# TIDA-01560_BlankSheet.net
KiCad netlist of a schematic drawn in Altium Designer
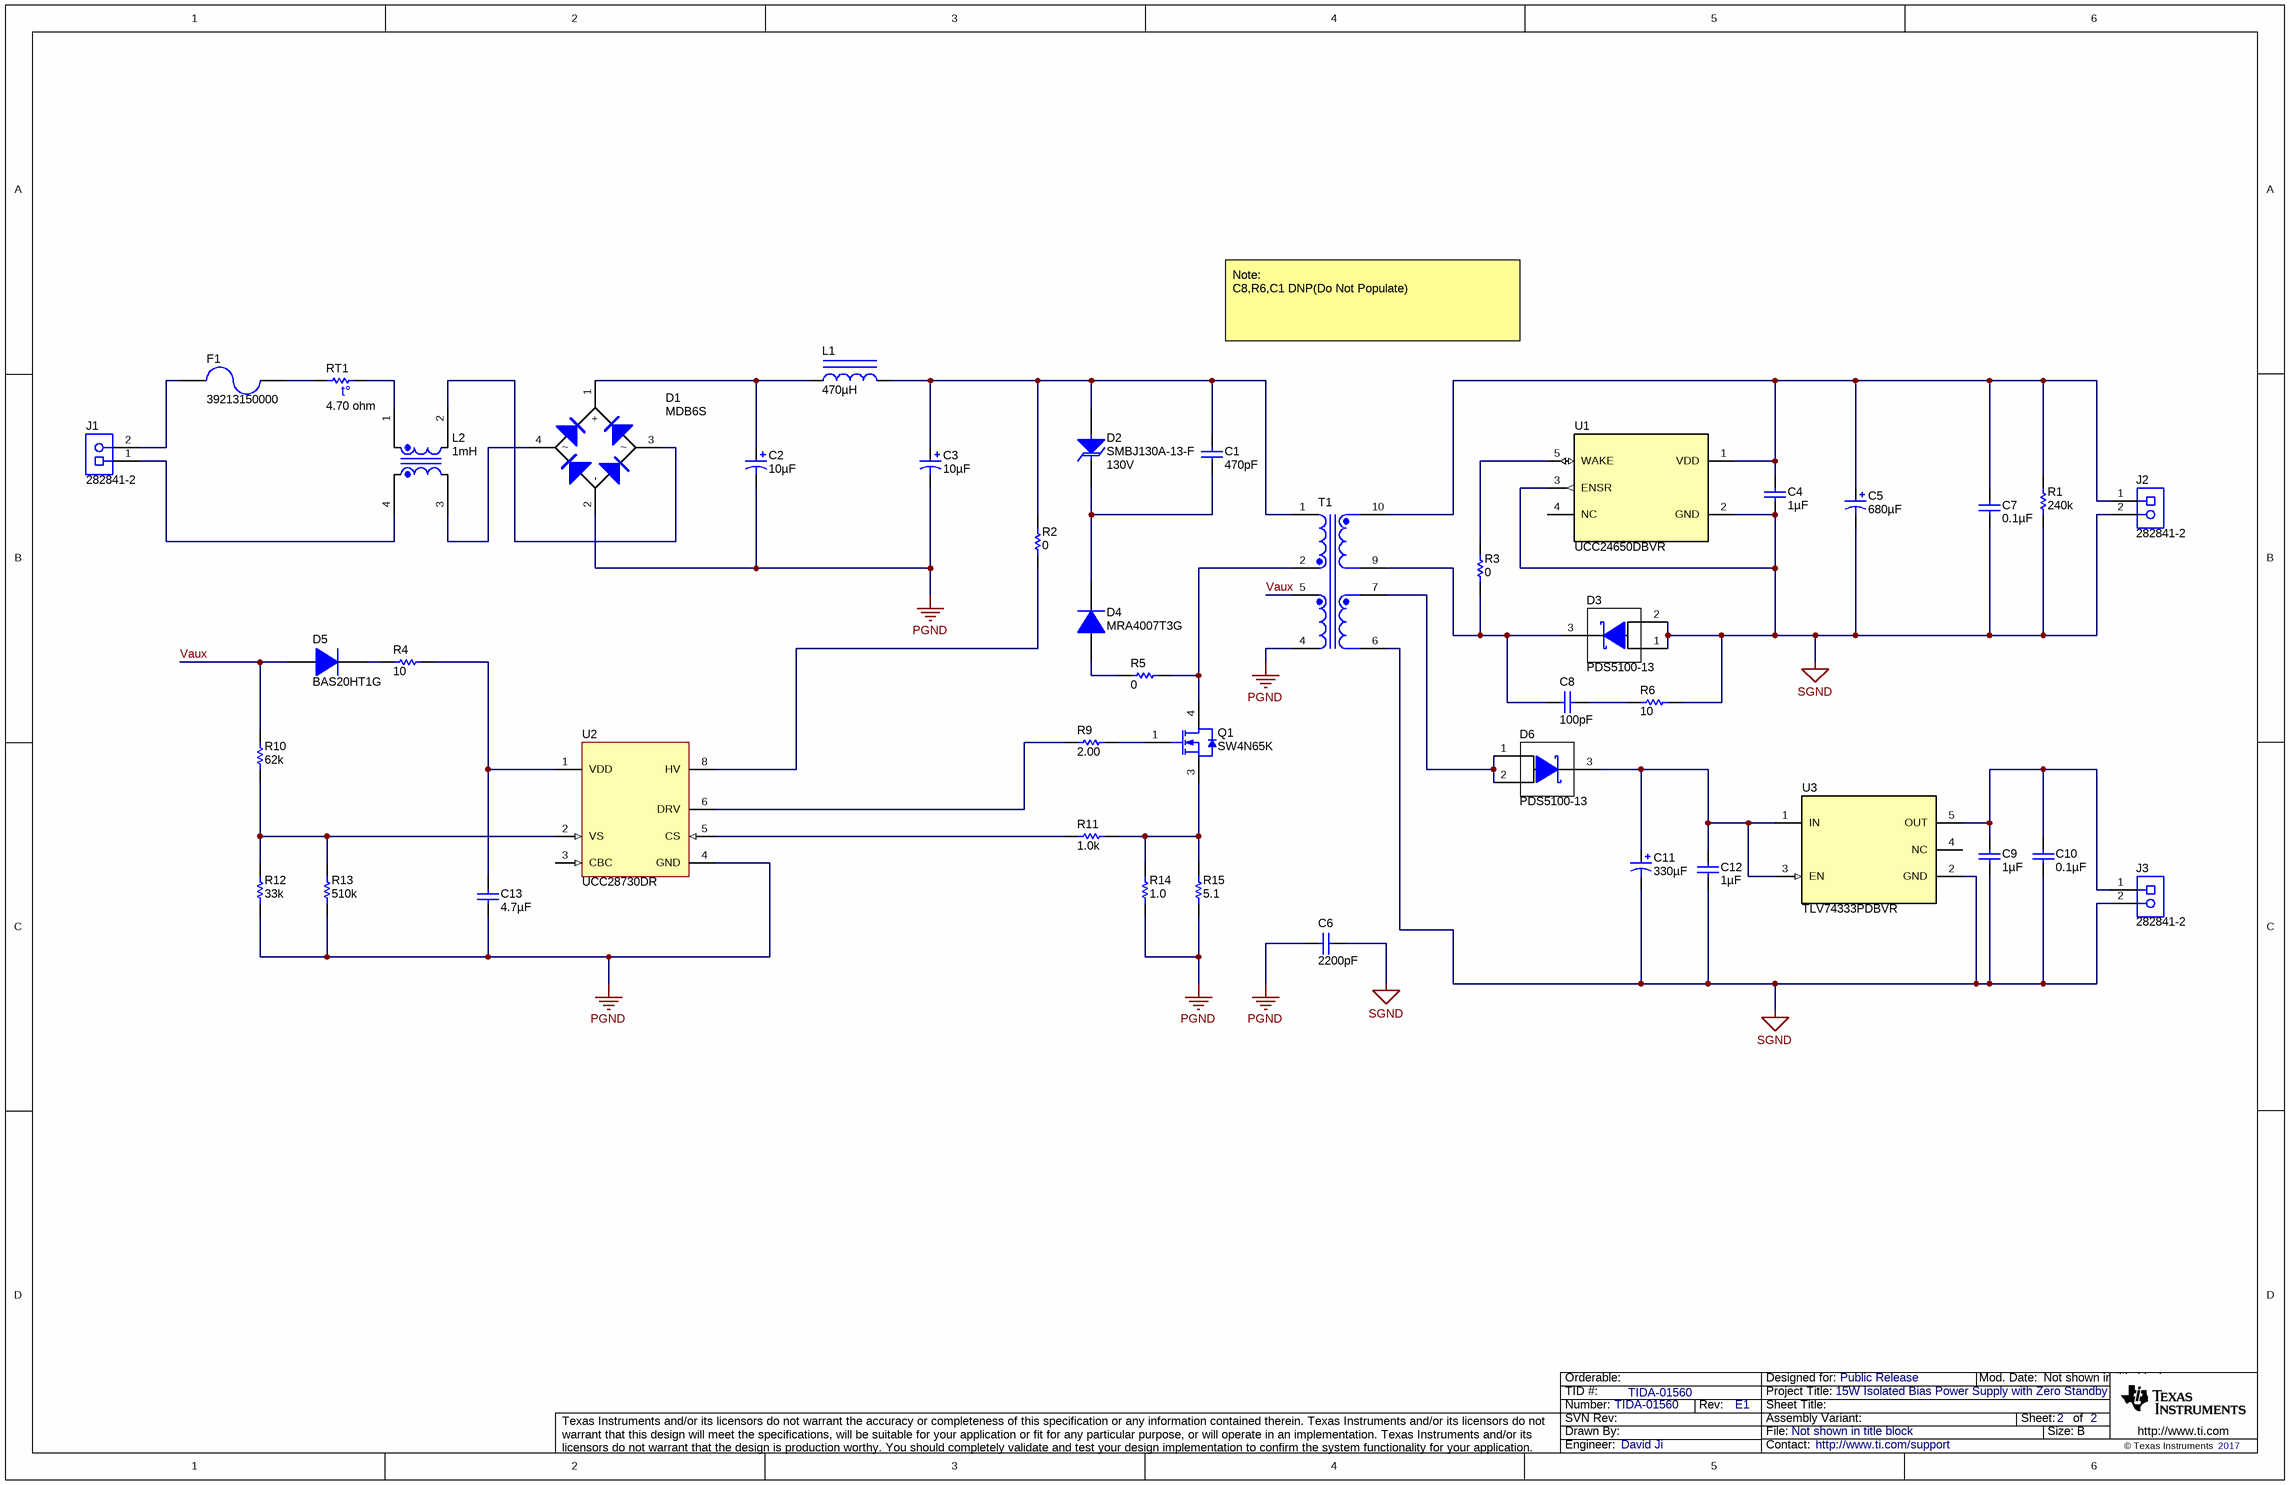
[diagram p0: TIDA-01560_BlankSheet.SchDoc]

(export (version "E")
  (design (tool "Eeschema 10.0.6"))
  (components
    (comp (ref "C1")
      (value "GRM31A7U2J471JW31D")
      (footprint "1206")
      (description "CAP, CERM, 470 pF, 630 V, +/- 5%, U2J, 1206")
      (fields
        (field (name "VALUEDISPLAYED") "470pF")
        (field (name "MANUFACTURER") "MuRata")
        (field (name "PUBLISHER") "Texas Instruments")
      )
      (libsource (lib "Capacitor_Ceramic") (part "GRM31A7U2J471JW31D"))
    )
    (comp (ref "C2")
      (value "UCY2G100MPD1TD")
      (footprint "CY_1000x1600")
      (description "CAP, AL, 10 µF, 400 V, +/- 20%, TH")
      (fields
        (field (name "VALUEDISPLAYED") "10µF")
        (field (name "MANUFACTURER") "Nichicon")
        (field (name "PUBLISHER") "Texas Instruments")
      )
      (libsource (lib "Capacitor_Aluminum") (part "UCY2G100MPD1TD"))
    )
    (comp (ref "C3")
      (value "UCY2G100MPD1TD")
      (footprint "CY_1000x1600")
      (description "CAP, AL, 10 µF, 400 V, +/- 20%, TH")
      (fields
        (field (name "VALUEDISPLAYED") "10µF")
        (field (name "MANUFACTURER") "Nichicon")
        (field (name "PUBLISHER") "Texas Instruments")
      )
      (libsource (lib "Capacitor_Aluminum") (part "UCY2G100MPD1TD"))
    )
    (comp (ref "C4")
      (value "06033C105KAT2A")
      (footprint "0603")
      (description "CAP, CERM, 1 µF, 25 V,+/- 10%, X7R, 0603")
      (fields
        (field (name "VALUEDISPLAYED") "1µF")
        (field (name "MANUFACTURER") "AVX")
        (field (name "PUBLISHER") "Texas Instruments")
      )
      (libsource (lib "Capacitor_Ceramic") (part "06033C105KAT2A"))
    )
    (comp (ref "C5")
      (value "APSG200ELL681MJB5S")
      (footprint "R7_1000x1250")
      (description "CAP, AL, 680 µF, 20 V, +/- 20%, 0.012 ohm, TH")
      (fields
        (field (name "VALUEDISPLAYED") "680µF")
        (field (name "MANUFACTURER") "Chemi-Con")
        (field (name "PUBLISHER") "Texas Instruments")
      )
      (libsource (lib "Capacitor_Aluminum") (part "RR71C331MDN1"))
    )
    (comp (ref "C6")
      (value "DE1E3KX222MN5AA01")
      (footprint "KX_1000x800x1400")
      (description "CAP, CERM, 2200 pF, X1 250 VAC/Y1 300 VAC, +/- 20%, E, 10.0x8.0x14.0mm")
      (fields
        (field (name "VALUEDISPLAYED") "2200pF")
        (field (name "MANUFACTURER") "MuRata")
        (field (name "PUBLISHER") "Texas Instruments")
      )
      (libsource (lib "Capacitor_Ceramic") (part "DE1E3KX222MN5AA01"))
    )
    (comp (ref "C7")
      (value "C0603C104K3RACTU")
      (footprint "0603")
      (description "CAP, CERM, 0.1 µF, 25 V,+/- 10%, X7R, 0603")
      (fields
        (field (name "VALUEDISPLAYED") "0.1µF")
        (field (name "MANUFACTURER") "Kemet")
        (field (name "PUBLISHER") "Texas Instruments")
      )
      (libsource (lib "Capacitor_Ceramic") (part "C0603C104K3RACTU"))
    )
    (comp (ref "C8")
      (value "GCM2165C2A101JA16D")
      (footprint "0805_HV")
      (description "CAP, CERM, 100 pF, 100 V,+/- 5%, C0G/NP0, AEC-Q200 Grade 1, 0805")
      (fields
        (field (name "VALUEDISPLAYED") "100pF")
        (field (name "MANUFACTURER") "MuRata")
        (field (name "PUBLISHER") "Texas Instruments")
      )
      (libsource (lib "Capacitor_Ceramic") (part "GCM2165C2A101JA16D"))
    )
    (comp (ref "C9")
      (value "C1608X7R1E105K080AB")
      (footprint "0603")
      (description "CAP, CERM, 1 µF, 25 V,+/- 10%, X7R, 0603")
      (fields
        (field (name "VALUEDISPLAYED") "1µF")
        (field (name "MANUFACTURER") "TDK")
        (field (name "PUBLISHER") "Texas Instruments")
      )
      (libsource (lib "Capacitor_Ceramic") (part "C1608X7R1E105K080AB"))
    )
    (comp (ref "C10")
      (value "C0603C104K3RACTU")
      (footprint "0603")
      (description "CAP, CERM, 0.1 µF, 25 V,+/- 10%, X7R, 0603")
      (fields
        (field (name "VALUEDISPLAYED") "0.1µF")
        (field (name "MANUFACTURER") "Kemet")
        (field (name "PUBLISHER") "Texas Instruments")
      )
      (libsource (lib "Capacitor_Ceramic") (part "C0603C104K3RACTU"))
    )
    (comp (ref "C11")
      (value "875105144010")
      (footprint "SM_RADIAL_6.3AMM")
      (description "CAP, AL, 330 µF, 6.3 V, +/- 20%, 0.020 ohm, SMD")
      (fields
        (field (name "VALUEDISPLAYED") "330µF")
        (field (name "MANUFACTURER") "Wurth Elektronik")
        (field (name "PUBLISHER") "Texas Instruments")
      )
      (libsource (lib "Capacitor_Aluminum") (part "UUD0J221MCL1GS"))
    )
    (comp (ref "C12")
      (value "C1608X7R1E105K080AB")
      (footprint "0603")
      (description "CAP, CERM, 1 µF, 25 V,+/- 10%, X7R, 0603")
      (fields
        (field (name "VALUEDISPLAYED") "1µF")
        (field (name "MANUFACTURER") "TDK")
        (field (name "PUBLISHER") "Texas Instruments")
      )
      (libsource (lib "Capacitor_Ceramic") (part "C1608X7R1E105K080AB"))
    )
    (comp (ref "C13")
      (value "C3216X7R1H475K160AC")
      (footprint "1206_180")
      (description "CAP, CERM, 4.7 µF, 50 V,+/- 10%, X7R, 1206")
      (fields
        (field (name "VALUEDISPLAYED") "4.7µF")
        (field (name "MANUFACTURER") "TDK")
        (field (name "PUBLISHER") "Texas Instruments")
      )
      (libsource (lib "Capacitor_Ceramic") (part "C3216X7R1H475K160AC"))
    )
    (comp (ref "D1")
      (value "MDB6S")
      (footprint "MICRODIP_4")
      (description "Diode, Switching-Bridge, 600 V, 1 A, MICRODIP_4")
      (fields
        (field (name "MANUFACTURER") "Fairchild Semiconductor")
        (field (name "PUBLISHER") "Texas Instruments")
      )
      (libsource (lib "Diode") (part "MDB6S"))
    )
    (comp (ref "D2")
      (value "SMBJ130A-13-F")
      (footprint "SMB")
      (description "Diode, TVS, Uni, 130 V, 209 Vc, SMB")
      (fields
        (field (name "ALTIUM_VALUE") "130V")
        (field (name "MANUFACTURER") "Diodes Inc.")
        (field (name "PUBLISHER") "Texas Instruments")
      )
      (libsource (lib "ZenerDiodes") (part "SMBJ130A-13-F"))
    )
    (comp (ref "D3")
      (value "PDS5100-13")
      (footprint "PowerDI5")
      (description "Diode, Schottky, 100 V, 5 A, PowerDI5")
      (fields (field (name "MANUFACTURER") "Diodes Inc.") (field (name "PUBLISHER") "Texas Instruments"))
      (libsource (lib "") (part "PDS5100-13_1"))
    )
    (comp (ref "D4")
      (value "MRA4007T3G")
      (footprint "SMA")
      (description "Diode, Standard Recovery Rectifier, 1000 V, 1 A, AEC-Q101, SMA")
      (fields (field (name "MANUFACTURER") "ON Semiconductor") (field (name "PUBLISHER") "Texas Instruments"))
      (libsource (lib "Diode") (part "MRA4007T3G"))
    )
    (comp (ref "D5")
      (value "BAS20HT1G")
      (footprint "sod-323")
      (description "Diode, Switching, 200 V, 0.2 A, AEC-Q101, SOD-323")
      (fields (field (name "MANUFACTURER") "ON Semiconductor") (field (name "PUBLISHER") "Texas Instruments"))
      (libsource (lib "Diode") (part "BAS20HT1G"))
    )
    (comp (ref "D6")
      (value "PDS5100-13")
      (footprint "PowerDI5")
      (description "Diode, Schottky, 100 V, 5 A, PowerDI5")
      (fields (field (name "MANUFACTURER") "Diodes Inc.") (field (name "PUBLISHER") "Texas Instruments"))
      (libsource (lib "Diode") (part "PDS5100-13"))
    )
    (comp (ref "F1")
      (value "39213150000")
      (footprint "FUSE_392")
      (description "Fuse, 3.15 A, 250VAC/VDC, TH")
      (fields (field (name "MANUFACTURER") "Littelfuse") (field (name "PUBLISHER") "Texas Instruments"))
      (libsource (lib "Fuse") (part "39213150000"))
    )
    (comp (ref "J1")
      (value "282841-2")
      (footprint "TEC_282841-2")
      (description "Terminal Block, 2x1, 5.08mm, TH")
      (fields
        (field (name "MANUFACTURER") "TE Connectivity")
        (field (name "SYMBOLCREATOR") "a0412235")
        (field (name "PUBLISHER") "Texas Instruments")
      )
      (libsource (lib "") (part "282841-2_1"))
    )
    (comp (ref "J2")
      (value "282841-2")
      (footprint "TEC_282841-2")
      (description "Terminal Block, 2x1, 5.08mm, TH")
      (fields
        (field (name "MANUFACTURER") "TE Connectivity")
        (field (name "SYMBOLCREATOR") "a0412235")
        (field (name "PUBLISHER") "Texas Instruments")
      )
      (libsource (lib "Connectors_TE_Connectivity") (part "282841-2"))
    )
    (comp (ref "J3")
      (value "282841-2")
      (footprint "TEC_282841-2")
      (description "Terminal Block, 2x1, 5.08mm, TH")
      (fields
        (field (name "MANUFACTURER") "TE Connectivity")
        (field (name "SYMBOLCREATOR") "a0412235")
        (field (name "PUBLISHER") "Texas Instruments")
      )
      (libsource (lib "Connectors_TE_Connectivity") (part "282841-2"))
    )
    (comp (ref "L1")
      (value "7447462471")
      (footprint "WE-TI_5075")
      (description "Inductor, Unshielded Drum Core, Ferrite, 470 µH, 0.35 A, 1.58 ohm, TH")
      (fields
        (field (name "VALUEDISPLAYED") "470µH")
        (field (name "MANUFACTURER") "Wurth Elektronik")
        (field (name "PUBLISHER") "Texas Instruments")
      )
      (libsource (lib "Inductor_Wurth") (part "7447462471"))
    )
    (comp (ref "L2")
      (value "744821201")
      (footprint "WE-CMB_XS")
      (description "Coupled inductor, 1 mH, 2 A, 0.045 ohm, TH")
      (fields
        (field (name "VALUEDISPLAYED") "1mH")
        (field (name "MANUFACTURER") "Wurth Elektronik")
        (field (name "SYMBOLCREATOR") "a0412235")
        (field (name "PUBLISHER") "Texas Instruments")
      )
      (libsource (lib "Coupled_Inductors") (part "744821201"))
    )
    (comp (ref "Q1")
      (value "SW4N65K")
      (footprint "TO-252")
      (description "MOSFET, N-CH, 650 V, 4 A, TO-252")
      (fields (field (name "MANUFACTURER") "IXYS") (field (name "PUBLISHER") "Texas Instruments"))
      (libsource (lib "FETs") (part "IXTY02N120P"))
    )
    (comp (ref "R1")
      (value "CRCW0805240KJNEA")
      (footprint "0805_HV")
      (description "RES, 240 k, 5%, 0.125 W, 0805")
      (fields
        (field (name "VALUEDISPLAYED") "240k")
        (field (name "MANUFACTURER") "Vishay-Dale")
        (field (name "PUBLISHER") "Texas Instruments")
      )
      (libsource (lib "Resistor_0805") (part "CRCW0805240KJNEA"))
    )
    (comp (ref "R2")
      (value "CRCW12060000Z0EA")
      (footprint "1206")
      (description "RES, 0, 5%, 0.25 W, 1206")
      (fields
        (field (name "VALUEDISPLAYED") "0")
        (field (name "MANUFACTURER") "Vishay-Dale")
        (field (name "PUBLISHER") "Texas Instruments")
      )
      (libsource (lib "Resistor_1206") (part "CRCW12060000Z0EA"))
    )
    (comp (ref "R3")
      (value "CRCW08050000Z0EA")
      (footprint "0805_HV")
      (description "RES, 0, 5%, 0.125 W, 0805")
      (fields
        (field (name "VALUEDISPLAYED") "0")
        (field (name "MANUFACTURER") "Vishay-Dale")
        (field (name "PUBLISHER") "Texas Instruments")
      )
      (libsource (lib "Resistor_0805") (part "CRCW08050000Z0EA"))
    )
    (comp (ref "R4")
      (value "CRCW080510R0JNEA")
      (footprint "0805_HV")
      (description "RES, 10, 5%, 0.125 W, 0805")
      (fields
        (field (name "VALUEDISPLAYED") "10")
        (field (name "MANUFACTURER") "Vishay-Dale")
        (field (name "PUBLISHER") "Texas Instruments")
      )
      (libsource (lib "Resistor_0805") (part "CRCW080510R0JNEA"))
    )
    (comp (ref "R5")
      (value "CRCW12060000Z0EA")
      (footprint "1206")
      (description "RES, 0, 5%, 0.25 W, 1206")
      (fields
        (field (name "VALUEDISPLAYED") "0")
        (field (name "MANUFACTURER") "Vishay-Dale")
        (field (name "PUBLISHER") "Texas Instruments")
      )
      (libsource (lib "Resistor_1206") (part "CRCW12060000Z0EA"))
    )
    (comp (ref "R6")
      (value "CRCW120610R0JNEA")
      (footprint "1206")
      (description "RES, 10, 5%, 0.25 W, 1206")
      (fields
        (field (name "VALUEDISPLAYED") "10")
        (field (name "MANUFACTURER") "Vishay-Dale")
        (field (name "PUBLISHER") "Texas Instruments")
      )
      (libsource (lib "Resistor_1206") (part "CRCW120610R0JNEA"))
    )
    (comp (ref "R9")
      (value "CRCW06032R00FKEA")
      (footprint "0603")
      (description "RES, 2.00, 1%, 0.1 W, 0603")
      (fields
        (field (name "VALUEDISPLAYED") "2.00")
        (field (name "MANUFACTURER") "Vishay-Dale")
        (field (name "PUBLISHER") "Texas Instruments")
      )
      (libsource (lib "Resistor_0603") (part "CRCW06032R00FKEA"))
    )
    (comp (ref "R10")
      (value "CRCW080562K0JNEA")
      (footprint "0805_HV")
      (description "RES, 62 k, 5%, 0.125 W, 0805")
      (fields
        (field (name "VALUEDISPLAYED") "62k")
        (field (name "MANUFACTURER") "Vishay-Dale")
        (field (name "PUBLISHER") "Texas Instruments")
      )
      (libsource (lib "Resistor_0805") (part "CRCW080562K0JNEA"))
    )
    (comp (ref "R11")
      (value "CRCW06031K00JNEA")
      (footprint "0603")
      (description "RES, 1.0 k, 5%, 0.1 W, 0603")
      (fields
        (field (name "VALUEDISPLAYED") "1.0k")
        (field (name "MANUFACTURER") "Vishay-Dale")
        (field (name "PUBLISHER") "Texas Instruments")
      )
      (libsource (lib "Resistor_0603") (part "CRCW06031K00JNEA"))
    )
    (comp (ref "R12")
      (value "CRCW060333K0JNEA")
      (footprint "0603")
      (description "RES, 33 k, 5%, 0.1 W, 0603")
      (fields
        (field (name "VALUEDISPLAYED") "33k")
        (field (name "MANUFACTURER") "Vishay-Dale")
        (field (name "PUBLISHER") "Texas Instruments")
      )
      (libsource (lib "Resistor_0603") (part "CRCW060333K0JNEA"))
    )
    (comp (ref "R13")
      (value "CRCW0603510KJNEA")
      (footprint "0603")
      (description "RES, 510 k, 5%, 0.1 W, 0603")
      (fields
        (field (name "VALUEDISPLAYED") "510k")
        (field (name "MANUFACTURER") "Vishay-Dale")
        (field (name "PUBLISHER") "Texas Instruments")
      )
      (libsource (lib "Resistor_0603") (part "CRCW0603510KJNEA"))
    )
    (comp (ref "R14")
      (value "CRCW08051R00JNEA")
      (footprint "0805_HV")
      (description "RES, 1.0, 5%, 0.125 W, 0805")
      (fields
        (field (name "VALUEDISPLAYED") "1.0")
        (field (name "MANUFACTURER") "Vishay-Dale")
        (field (name "PUBLISHER") "Texas Instruments")
      )
      (libsource (lib "Resistor_0805") (part "CRCW08051R00JNEA"))
    )
    (comp (ref "R15")
      (value "CRCW08055R10JNEA")
      (footprint "0805_HV")
      (description "RES, 5.1, 5%, 0.125 W, 0805")
      (fields
        (field (name "VALUEDISPLAYED") "5.1")
        (field (name "MANUFACTURER") "Vishay-Dale")
        (field (name "PUBLISHER") "Texas Instruments")
      )
      (libsource (lib "Resistor_0805") (part "CRCW08055R10JNEA"))
    )
    (comp (ref "RT1")
      (value "4.70 ohm")
      (footprint "S153")
      (description "Thermistor NTC, 4.70 ohm, 20%, 8.5mm Disc")
      (fields
        (field (name "PARTNUMBER") "B57153S0479M051")
        (field (name "MANUFACTURER") "TDK")
        (field (name "PUBLISHER") "Texas Instruments")
      )
      (libsource (lib "ThermistorNTC") (part "B57153S0479M051"))
    )
    (comp (ref "T1")
      (value "750343769,Rev02")
      (footprint "EFD20 Transformer:PCBComponent_1")
      (description "Transformer, 620uH, TH")
      (fields (field (name "MANUFACTURER") "Wurth Elektronik") (field (name "SYMBOLCREATOR") "Use a-id"))
      (libsource (lib "EFD20 Transformer") (part "Component_1"))
    )
    (comp (ref "U1")
      (value "UCC24650DBVR")
      (footprint "DBV0005A_N")
      (description "200-V Wake-Up Monitor for Fast Transient PSR, DBV0005A")
      (fields
        (field (name "ALTERNATE PARTNUMBER") "UCC24650DBVT")
        (field (name "MANUFACTURER") "Texas Instruments")
        (field (name "SYMBOLCREATOR") "x0208326")
        (field (name "PUBLISHER") "Texas Instruments")
      )
      (libsource (lib "TI_Pre_Release") (part "UCC24650DBVR"))
    )
    (comp (ref "U2")
      (value "UCC28730DR")
      (footprint "D0007A_N")
      (description "Constant-Voltage Constant-Current Flyback Controller With PSR and Wake-Up Monitoring, D0007A")
      (fields
        (field (name "ALTERNATE PARTNUMBER") "UCC28730D")
        (field (name "MANUFACTURER") "Texas Instruments")
        (field (name "SYMBOLCREATOR") "x0208325")
        (field (name "PUBLISHER") "Texas Instruments")
      )
      (libsource (lib "TI_Pre_Release1") (part "UCC28730DR"))
    )
    (comp (ref "U3")
      (value "TLV74333PDBVR")
      (footprint "DBV0005A_N")
      (description "Low-Dropout Regulator, DBV0005A (SOT-23-5)")
      (fields
        (field (name "MANUFACTURER") "Texas Instruments")
        (field (name "SYMBOLCREATOR") "Altium")
        (field (name "PUBLISHER") "Texas Instruments")
      )
      (libsource (lib "TI_Pre_RTM") (part "TLV74333PDBVR"))
    )
  )
  (nets
    (net (code "1") (name "/Vaux") (class "Default")
      (node (ref "D5") (pin "2") (pinfunction "A_2") (pintype "passive"))
      (node (ref "R10") (pin "1") (pinfunction "1_1") (pintype "passive"))
      (node (ref "T1") (pin "5") (pinfunction "5_5") (pintype "passive"))
    )
    (net (code "2") (name "Net-(C2-+)") (class "Default")
      (node (ref "C2") (pin "1") (pinfunction "+_1") (pintype "passive"))
      (node (ref "D1") (pin "1") (pinfunction "+_1") (pintype "passive"))
      (node (ref "L1") (pin "1") (pinfunction "1_1") (pintype "passive"))
    )
    (net (code "3") (name "Net-(C3-+)") (class "Default")
      (node (ref "C1") (pin "1") (pinfunction "1_1") (pintype "passive"))
      (node (ref "C3") (pin "1") (pinfunction "+_1") (pintype "passive"))
      (node (ref "D2") (pin "2") (pinfunction "A_2") (pintype "passive"))
      (node (ref "L1") (pin "2") (pinfunction "2_2") (pintype "passive"))
      (node (ref "R2") (pin "2") (pinfunction "2_2") (pintype "passive"))
      (node (ref "T1") (pin "1") (pinfunction "1_1") (pintype "passive"))
    )
    (net (code "4") (name "Net-(C5-+)") (class "Default")
      (node (ref "C4") (pin "1") (pinfunction "1_1") (pintype "passive"))
      (node (ref "C5") (pin "1") (pinfunction "+_1") (pintype "passive"))
      (node (ref "C7") (pin "1") (pinfunction "1_1") (pintype "passive"))
      (node (ref "J2") (pin "1") (pinfunction "1_1") (pintype "passive"))
      (node (ref "R1") (pin "2") (pinfunction "2_2") (pintype "passive"))
      (node (ref "T1") (pin "10") (pinfunction "10_10") (pintype "passive"))
      (node (ref "U1") (pin "1") (pinfunction "VDD_1") (pintype "power_in"))
    )
    (net (code "5") (name "Net-(C8-Pad1)") (class "Default")
      (node (ref "C8") (pin "1") (pinfunction "1_1") (pintype "passive"))
      (node (ref "R6") (pin "1") (pinfunction "1_1") (pintype "passive"))
    )
    (net (code "6") (name "Net-(C11-+)") (class "Default")
      (node (ref "C11") (pin "1") (pinfunction "+_1") (pintype "passive"))
      (node (ref "C12") (pin "1") (pinfunction "1_1") (pintype "passive"))
      (node (ref "D6") (pin "3") (pinfunction "K_3") (pintype "passive"))
      (node (ref "U3") (pin "1") (pinfunction "IN_1") (pintype "power_in"))
      (node (ref "U3") (pin "3") (pinfunction "EN_3") (pintype "input"))
    )
    (net (code "7") (name "Net-(D1-~-Pad3)") (class "Default")
      (node (ref "D1") (pin "3") (pinfunction "~_3") (pintype "passive"))
      (node (ref "L2") (pin "2") (pinfunction "2_2") (pintype "passive"))
    )
    (net (code "8") (name "Net-(D1-~-Pad4)") (class "Default")
      (node (ref "D1") (pin "4") (pinfunction "~_4") (pintype "passive"))
      (node (ref "L2") (pin "3") (pinfunction "3_3") (pintype "passive"))
    )
    (net (code "9") (name "Net-(D2-K)") (class "Default")
      (node (ref "C1") (pin "2") (pinfunction "2_2") (pintype "passive"))
      (node (ref "D2") (pin "1") (pinfunction "K_1") (pintype "passive"))
      (node (ref "D4") (pin "1") (pinfunction "K_1") (pintype "passive"))
    )
    (net (code "10") (name "Net-(D3-K)") (class "Default")
      (node (ref "C8") (pin "2") (pinfunction "2_2") (pintype "passive"))
      (node (ref "D3") (pin "3") (pinfunction "K_3") (pintype "passive"))
      (node (ref "R3") (pin "1") (pinfunction "1_1") (pintype "passive"))
      (node (ref "T1") (pin "9") (pinfunction "9_9") (pintype "passive"))
    )
    (net (code "11") (name "Net-(D4-A)") (class "Default")
      (node (ref "D4") (pin "2") (pinfunction "A_2") (pintype "passive"))
      (node (ref "R5") (pin "1") (pinfunction "1_1") (pintype "passive"))
    )
    (net (code "12") (name "Net-(D5-K)") (class "Default")
      (node (ref "D5") (pin "1") (pinfunction "K_1") (pintype "passive"))
      (node (ref "R4") (pin "1") (pinfunction "1_1") (pintype "passive"))
    )
    (net (code "13") (name "Net-(D6-A-Pad1)") (class "Default")
      (node (ref "D6") (pin "1") (pinfunction "A_1") (pintype "passive"))
      (node (ref "D6") (pin "2") (pinfunction "A_2") (pintype "passive"))
      (node (ref "T1") (pin "7") (pinfunction "7_7") (pintype "passive"))
    )
    (net (code "14") (name "Net-(F1-Pad1)") (class "Default")
      (node (ref "F1") (pin "1") (pinfunction "1_1") (pintype "passive"))
      (node (ref "RT1") (pin "1") (pinfunction "1_1") (pintype "passive"))
    )
    (net (code "15") (name "Net-(F1-Pad2)") (class "Default")
      (node (ref "F1") (pin "2") (pinfunction "2_2") (pintype "passive"))
      (node (ref "J1") (pin "2") (pinfunction "2_2") (pintype "passive"))
    )
    (net (code "16") (name "Net-(J1-Pad1)") (class "Default")
      (node (ref "J1") (pin "1") (pinfunction "1_1") (pintype "passive"))
      (node (ref "L2") (pin "4") (pinfunction "4_4") (pintype "passive"))
    )
    (net (code "17") (name "Net-(L2-Pad1)") (class "Default")
      (node (ref "L2") (pin "1") (pinfunction "1_1") (pintype "passive"))
      (node (ref "RT1") (pin "2") (pinfunction "2_2") (pintype "passive"))
    )
    (net (code "18") (name "Net-(Q1-D)") (class "Default")
      (node (ref "Q1") (pin "4") (pinfunction "D_4") (pintype "passive"))
      (node (ref "R5") (pin "2") (pinfunction "2_2") (pintype "passive"))
      (node (ref "T1") (pin "2") (pinfunction "2_2") (pintype "passive"))
    )
    (net (code "19") (name "Net-(Q1-G)") (class "Default")
      (node (ref "Q1") (pin "1") (pinfunction "G_1") (pintype "passive"))
      (node (ref "R9") (pin "2") (pinfunction "2_2") (pintype "passive"))
    )
    (net (code "20") (name "Net-(Q1-S)") (class "Default")
      (node (ref "Q1") (pin "3") (pinfunction "S_3") (pintype "passive"))
      (node (ref "R11") (pin "2") (pinfunction "2_2") (pintype "passive"))
      (node (ref "R14") (pin "2") (pinfunction "2_2") (pintype "passive"))
      (node (ref "R15") (pin "2") (pinfunction "2_2") (pintype "passive"))
    )
    (net (code "21") (name "Net-(U1-WAKE)") (class "Default")
      (node (ref "R3") (pin "2") (pinfunction "2_2") (pintype "passive"))
      (node (ref "U1") (pin "5") (pinfunction "WAKE_5") (pintype "bidirectional"))
    )
    (net (code "22") (name "Net-(U2-CS)") (class "Default")
      (node (ref "R11") (pin "1") (pinfunction "1_1") (pintype "passive"))
      (node (ref "U2") (pin "5") (pinfunction "CS_5") (pintype "input"))
    )
    (net (code "23") (name "Net-(U2-DRV)") (class "Default")
      (node (ref "R9") (pin "1") (pinfunction "1_1") (pintype "passive"))
      (node (ref "U2") (pin "6") (pinfunction "DRV_6") (pintype "power_in"))
    )
    (net (code "24") (name "Net-(U2-HV)") (class "Default")
      (node (ref "R2") (pin "1") (pinfunction "1_1") (pintype "passive"))
      (node (ref "U2") (pin "8") (pinfunction "HV_8") (pintype "power_in"))
    )
    (net (code "25") (name "Net-(U2-VDD)") (class "Default")
      (node (ref "C13") (pin "1") (pinfunction "1_1") (pintype "passive"))
      (node (ref "R4") (pin "2") (pinfunction "2_2") (pintype "passive"))
      (node (ref "U2") (pin "1") (pinfunction "VDD_1") (pintype "power_in"))
    )
    (net (code "26") (name "Net-(U2-VS)") (class "Default")
      (node (ref "R10") (pin "2") (pinfunction "2_2") (pintype "passive"))
      (node (ref "R12") (pin "2") (pinfunction "2_2") (pintype "passive"))
      (node (ref "R13") (pin "2") (pinfunction "2_2") (pintype "passive"))
      (node (ref "U2") (pin "2") (pinfunction "VS_2") (pintype "input"))
    )
    (net (code "27") (name "Net-(U3-OUT)") (class "Default")
      (node (ref "C10") (pin "1") (pinfunction "1_1") (pintype "passive"))
      (node (ref "C9") (pin "1") (pinfunction "1_1") (pintype "passive"))
      (node (ref "J3") (pin "1") (pinfunction "1_1") (pintype "passive"))
      (node (ref "U3") (pin "5") (pinfunction "OUT_5") (pintype "power_in"))
    )
    (net (code "28") (name "PGND") (class "Default")
      (node (ref "C13") (pin "2") (pinfunction "2_2") (pintype "passive"))
      (node (ref "C2") (pin "2") (pinfunction "-_2") (pintype "passive"))
      (node (ref "C3") (pin "2") (pinfunction "-_2") (pintype "passive"))
      (node (ref "C6") (pin "2") (pinfunction "2_2") (pintype "passive"))
      (node (ref "D1") (pin "2") (pinfunction "-_2") (pintype "passive"))
      (node (ref "R12") (pin "1") (pinfunction "1_1") (pintype "passive"))
      (node (ref "R13") (pin "1") (pinfunction "1_1") (pintype "passive"))
      (node (ref "R14") (pin "1") (pinfunction "1_1") (pintype "passive"))
      (node (ref "R15") (pin "1") (pinfunction "1_1") (pintype "passive"))
      (node (ref "T1") (pin "4") (pinfunction "4_4") (pintype "passive"))
      (node (ref "U2") (pin "4") (pinfunction "GND_4") (pintype "power_in"))
    )
    (net (code "29") (name "SGND") (class "Default")
      (node (ref "C10") (pin "2") (pinfunction "2_2") (pintype "passive"))
      (node (ref "C11") (pin "2") (pinfunction "-_2") (pintype "passive"))
      (node (ref "C12") (pin "2") (pinfunction "2_2") (pintype "passive"))
      (node (ref "C4") (pin "2") (pinfunction "2_2") (pintype "passive"))
      (node (ref "C5") (pin "2") (pinfunction "-_2") (pintype "passive"))
      (node (ref "C6") (pin "1") (pinfunction "1_1") (pintype "passive"))
      (node (ref "C7") (pin "2") (pinfunction "2_2") (pintype "passive"))
      (node (ref "C9") (pin "2") (pinfunction "2_2") (pintype "passive"))
      (node (ref "D3") (pin "1") (pinfunction "A_1") (pintype "passive"))
      (node (ref "D3") (pin "2") (pinfunction "A_2") (pintype "passive"))
      (node (ref "J2") (pin "2") (pinfunction "2_2") (pintype "passive"))
      (node (ref "J3") (pin "2") (pinfunction "2_2") (pintype "passive"))
      (node (ref "R1") (pin "1") (pinfunction "1_1") (pintype "passive"))
      (node (ref "R6") (pin "2") (pinfunction "2_2") (pintype "passive"))
      (node (ref "T1") (pin "6") (pinfunction "6_6") (pintype "passive"))
      (node (ref "U1") (pin "2") (pinfunction "GND_2") (pintype "power_in"))
      (node (ref "U1") (pin "3") (pinfunction "ENSR_3") (pintype "output"))
      (node (ref "U3") (pin "2") (pinfunction "GND_2") (pintype "power_in"))
    )
    (net (code "30") (name "unconnected-(U1-NC-Pad4)") (class "Default")
      (node (ref "U1") (pin "4") (pinfunction "NC_4") (pintype "passive"))
    )
    (net (code "31") (name "unconnected-(U2-CBC-Pad3)") (class "Default")
      (node (ref "U2") (pin "3") (pinfunction "CBC_3") (pintype "input"))
    )
    (net (code "32") (name "unconnected-(U3-NC-Pad4)") (class "Default")
      (node (ref "U3") (pin "4") (pinfunction "NC_4") (pintype "passive"))
    )
  )
)
